# EEGAmp_SMT_MountHole.net
KiCad netlist of a schematic drawn in EAGLE
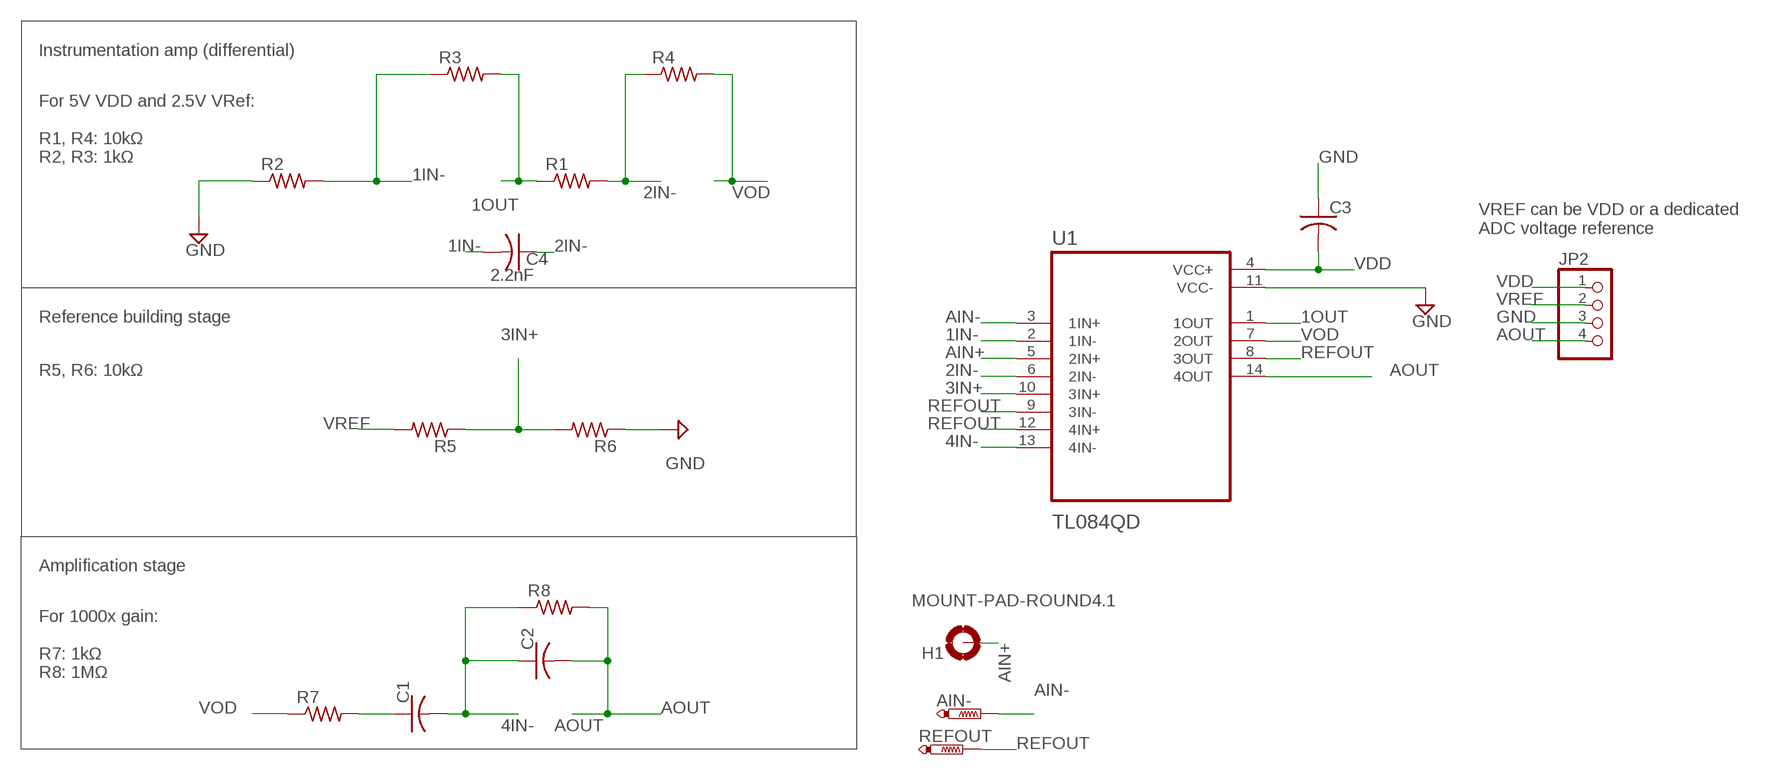
[diagram p0: schematic, sheet 1]

(export (version "E")
  (design (tool "Eeschema 10.0.6"))
  (components
    (comp (ref "AIN-")
      (value "PTR1PAD1-17")
      (footprint "eagle-import:P1-17")
      (libsource (lib "eagle-import") (part "PTR1PAD1-17"))
    )
    (comp (ref "C1")
      (value "C-USC0402")
      (footprint "eagle-import:C0402")
      (libsource (lib "eagle-import") (part "C-USC0402"))
    )
    (comp (ref "C2")
      (value "C-USC0402")
      (footprint "eagle-import:C0402")
      (libsource (lib "eagle-import") (part "C-USC0402"))
    )
    (comp (ref "C3")
      (value "C-USC0402")
      (footprint "eagle-import:C0402")
      (libsource (lib "eagle-import") (part "C-USC0402"))
    )
    (comp (ref "C4")
      (value "2.2nF")
      (footprint "eagle-import:C0402")
      (libsource (lib "eagle-import") (part "C-USC0402"))
    )
    (comp (ref "H1")
      (value "MOUNT-PAD-ROUND4.1")
      (footprint "eagle-import:4,1-PAD")
      (libsource (lib "eagle-import") (part "MOUNT-PAD-ROUND4.1"))
    )
    (comp (ref "JP2")
      (value "PINHD-1X4")
      (footprint "eagle-import:1X04")
      (libsource (lib "eagle-import") (part "PINHD-1X4"))
    )
    (comp (ref "R1")
      (value "R-US_R0402")
      (footprint "eagle-import:R0402")
      (libsource (lib "eagle-import") (part "R-US_R0402"))
    )
    (comp (ref "R2")
      (value "R-US_R0402")
      (footprint "eagle-import:R0402")
      (libsource (lib "eagle-import") (part "R-US_R0402"))
    )
    (comp (ref "R3")
      (value "R-US_R0402")
      (footprint "eagle-import:R0402")
      (libsource (lib "eagle-import") (part "R-US_R0402"))
    )
    (comp (ref "R4")
      (value "R-US_R0402")
      (footprint "eagle-import:R0402")
      (libsource (lib "eagle-import") (part "R-US_R0402"))
    )
    (comp (ref "R5")
      (value "R-US_R0402")
      (footprint "eagle-import:R0402")
      (libsource (lib "eagle-import") (part "R-US_R0402"))
    )
    (comp (ref "R6")
      (value "R-US_R0402")
      (footprint "eagle-import:R0402")
      (libsource (lib "eagle-import") (part "R-US_R0402"))
    )
    (comp (ref "R7")
      (value "R-US_R0402")
      (footprint "eagle-import:R0402")
      (libsource (lib "eagle-import") (part "R-US_R0402"))
    )
    (comp (ref "R8")
      (value "R-US_R0402")
      (footprint "eagle-import:R0402")
      (libsource (lib "eagle-import") (part "R-US_R0402"))
    )
    (comp (ref "REFOUT")
      (value "PTR1PAD1-17")
      (footprint "eagle-import:P1-17")
      (libsource (lib "eagle-import") (part "PTR1PAD1-17"))
    )
    (comp (ref "U1")
      (value "TL084QD")
      (footprint "eagle-import:SOIC127P600X175-14N")
      (fields (field (name "MF") "Texas Instruments"))
      (libsource (lib "eagle-import") (part "TL084QD"))
    )
  )
  (nets
    (net (code "1") (name "/1IN-") (class "Default")
      (node (ref "C4") (pin "2") (pinfunction "2_2") (pintype "passive"))
      (node (ref "R2") (pin "2") (pinfunction "2_2") (pintype "passive"))
      (node (ref "R3") (pin "1") (pinfunction "1_1") (pintype "passive"))
      (node (ref "U1") (pin "2") (pinfunction "1IN-_2") (pintype "input"))
    )
    (net (code "2") (name "/1OUT") (class "Default")
      (node (ref "R1") (pin "1") (pinfunction "1_1") (pintype "passive"))
      (node (ref "R3") (pin "2") (pinfunction "2_2") (pintype "passive"))
      (node (ref "U1") (pin "1") (pinfunction "1OUT_1") (pintype "output"))
    )
    (net (code "3") (name "/2IN-") (class "Default")
      (node (ref "C4") (pin "1") (pinfunction "1_1") (pintype "passive"))
      (node (ref "R1") (pin "2") (pinfunction "2_2") (pintype "passive"))
      (node (ref "R4") (pin "1") (pinfunction "1_1") (pintype "passive"))
      (node (ref "U1") (pin "6") (pinfunction "2IN-_6") (pintype "input"))
    )
    (net (code "4") (name "/3IN+") (class "Default")
      (node (ref "R5") (pin "1") (pinfunction "1_1") (pintype "passive"))
      (node (ref "R6") (pin "2") (pinfunction "2_2") (pintype "passive"))
      (node (ref "U1") (pin "10") (pinfunction "3IN+_10") (pintype "input"))
    )
    (net (code "5") (name "/4IN-") (class "Default")
      (node (ref "C1") (pin "2") (pinfunction "2_2") (pintype "passive"))
      (node (ref "C2") (pin "1") (pinfunction "1_1") (pintype "passive"))
      (node (ref "R8") (pin "1") (pinfunction "1_1") (pintype "passive"))
      (node (ref "U1") (pin "13") (pinfunction "4IN-_13") (pintype "input"))
    )
    (net (code "6") (name "/AIN+") (class "Default")
      (node (ref "H1") (pin "B4,1") (pinfunction "MOUNT_B4,1") (pintype "passive"))
      (node (ref "U1") (pin "5") (pinfunction "2IN+_5") (pintype "input"))
    )
    (net (code "7") (name "/AIN-") (class "Default")
      (node (ref "AIN-") (pin "TP") (pinfunction "TP_TP") (pintype "input"))
      (node (ref "U1") (pin "3") (pinfunction "1IN+_3") (pintype "input"))
    )
    (net (code "8") (name "/AOUT") (class "Default")
      (node (ref "C2") (pin "2") (pinfunction "2_2") (pintype "passive"))
      (node (ref "JP2") (pin "4") (pinfunction "4_4") (pintype "passive"))
      (node (ref "R8") (pin "2") (pinfunction "2_2") (pintype "passive"))
      (node (ref "U1") (pin "14") (pinfunction "4OUT_14") (pintype "output"))
    )
    (net (code "9") (name "/REFOUT") (class "Default")
      (node (ref "REFOUT") (pin "TP") (pinfunction "TP_TP") (pintype "input"))
      (node (ref "U1") (pin "12") (pinfunction "4IN+_12") (pintype "input"))
      (node (ref "U1") (pin "8") (pinfunction "3OUT_8") (pintype "output"))
      (node (ref "U1") (pin "9") (pinfunction "3IN-_9") (pintype "input"))
    )
    (net (code "10") (name "/VDD") (class "Default")
      (node (ref "C3") (pin "2") (pinfunction "2_2") (pintype "passive"))
      (node (ref "JP2") (pin "1") (pinfunction "1_1") (pintype "passive"))
      (node (ref "U1") (pin "4") (pinfunction "VCC+_4") (pintype "power_in"))
    )
    (net (code "11") (name "/VOD") (class "Default")
      (node (ref "R4") (pin "2") (pinfunction "2_2") (pintype "passive"))
      (node (ref "R7") (pin "1") (pinfunction "1_1") (pintype "passive"))
      (node (ref "U1") (pin "7") (pinfunction "2OUT_7") (pintype "output"))
    )
    (net (code "12") (name "/VREF") (class "Default")
      (node (ref "JP2") (pin "2") (pinfunction "2_2") (pintype "passive"))
      (node (ref "R5") (pin "2") (pinfunction "2_2") (pintype "passive"))
    )
    (net (code "13") (name "GND") (class "Default")
      (node (ref "C3") (pin "1") (pinfunction "1_1") (pintype "passive"))
      (node (ref "JP2") (pin "3") (pinfunction "3_3") (pintype "passive"))
      (node (ref "R2") (pin "1") (pinfunction "1_1") (pintype "passive"))
      (node (ref "R6") (pin "1") (pinfunction "1_1") (pintype "passive"))
      (node (ref "U1") (pin "11") (pinfunction "VCC-_11") (pintype "power_in"))
    )
    (net (code "14") (name "Net-(C1-Pad1)") (class "Default")
      (node (ref "C1") (pin "1") (pinfunction "1_1") (pintype "passive"))
      (node (ref "R7") (pin "2") (pinfunction "2_2") (pintype "passive"))
    )
  )
)
